# OmapSystem.net
KiCad netlist of a schematic drawn in Altium Designer
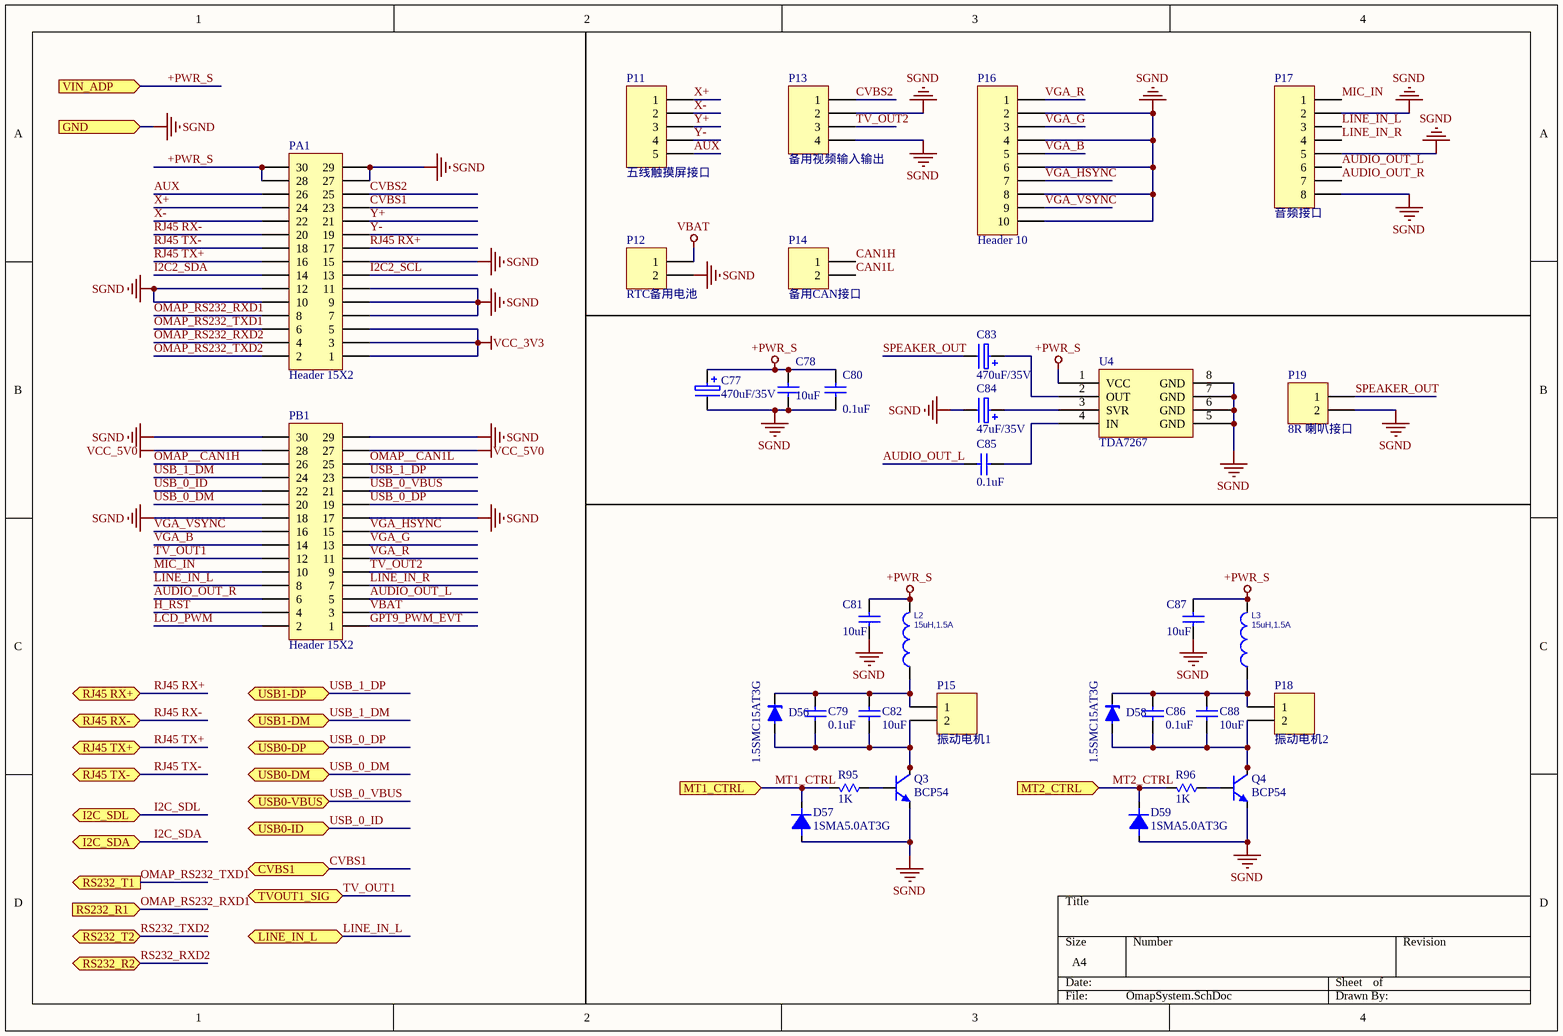
[diagram p0: OmapSystem.SchDoc]

(export (version "E")
  (design (tool "Eeschema 10.0.6"))
  (components
    (comp (ref "C77")
      (value "470uF/35V")
      (footprint "CT7343-E")
      (description "Electrolytic Capacitor")
      (libsource (lib "*") (part "ELECTRO"))
    )
    (comp (ref "C78")
      (value "10uF")
      (footprint "C1206")
      (description "CAP")
      (fields (field (name "PUBLISHER") "Altium Limited"))
      (libsource (lib "Passive Components Class") (part "CAP"))
    )
    (comp (ref "C79")
      (value "0.1uF")
      (footprint "C0805")
      (description "Capacitor")
      (fields (field (name "PUBLISHER") "Altium Limited"))
      (libsource (lib "Miscellaneous Devices") (part "Cap"))
    )
    (comp (ref "C80")
      (value "0.1uF")
      (footprint "C0805")
      (description "CAP")
      (fields (field (name "PUBLISHER") "Altium Limited"))
      (libsource (lib "Passive Components Class") (part "CAP"))
    )
    (comp (ref "C81")
      (value "10uF")
      (footprint "C1206")
      (description "CAP")
      (fields (field (name "PUBLISHER") "Altium Limited"))
      (libsource (lib "Passive Components Class") (part "CAP"))
    )
    (comp (ref "C82")
      (value "10uF")
      (footprint "C1206")
      (description "CAP")
      (fields (field (name "PUBLISHER") "Altium Limited"))
      (libsource (lib "Passive Components Class") (part "CAP"))
    )
    (comp (ref "C83")
      (value "470uF/35V")
      (footprint "CT7343-E")
      (description "Electrolytic Capacitor")
      (libsource (lib "*") (part "ELECTRO"))
    )
    (comp (ref "C84")
      (value "47uF/35V")
      (footprint "CT7343-D")
      (description "Electrolytic Capacitor")
      (libsource (lib "*") (part "ELECTRO"))
    )
    (comp (ref "C85")
      (value "0.1uF")
      (footprint "C0805")
      (description "Capacitor")
      (fields (field (name "PUBLISHER") "Altium Limited"))
      (libsource (lib "Miscellaneous Devices") (part "Cap"))
    )
    (comp (ref "C86")
      (value "0.1uF")
      (footprint "C0805")
      (description "Capacitor")
      (fields (field (name "PUBLISHER") "Altium Limited"))
      (libsource (lib "Miscellaneous Devices") (part "Cap"))
    )
    (comp (ref "C87")
      (value "10uF")
      (footprint "C1206")
      (description "CAP")
      (fields (field (name "PUBLISHER") "Altium Limited"))
      (libsource (lib "Passive Components Class") (part "CAP"))
    )
    (comp (ref "C88")
      (value "10uF")
      (footprint "C1206")
      (description "CAP")
      (fields (field (name "PUBLISHER") "Altium Limited"))
      (libsource (lib "Passive Components Class") (part "CAP"))
    )
    (comp (ref "D56")
      (value "1.5SMC15AT3G")
      (footprint "SMC")
      (description "Small Signal Zener Diodes")
      (libsource (lib "Passive Components Class") (part "DIODE-ZENER"))
    )
    (comp (ref "D57")
      (value "1SMA5.0AT3G")
      (footprint "SMA")
      (description "Diode")
      (libsource (lib "*") (part "DIODE1"))
    )
    (comp (ref "D58")
      (value "1.5SMC15AT3G")
      (footprint "SMC")
      (description "Small Signal Zener Diodes")
      (libsource (lib "Passive Components Class") (part "DIODE-ZENER"))
    )
    (comp (ref "D59")
      (value "1SMA5.0AT3G")
      (footprint "SMA")
      (description "Diode")
      (libsource (lib "*") (part "DIODE1"))
    )
    (comp (ref "L2")
      (value "15uH,1.5A")
      (footprint "L3030-P")
      (description "Inductor")
      (fields (field (name "PUBLISHER") "Altium Limited"))
      (libsource (lib "Miscellaneous Devices") (part "Inductor"))
    )
    (comp (ref "L3")
      (value "15uH,1.5A")
      (footprint "L3030-P")
      (description "Inductor")
      (fields (field (name "PUBLISHER") "Altium Limited"))
      (libsource (lib "Miscellaneous Devices") (part "Inductor"))
    )
    (comp (ref "P11")
      (value "五线触摸屏接口")
      (footprint "DS1X5-2.54")
      (description "Header, 5-Pin")
      (fields (field (name "PUBLISHER") "Altium Limited"))
      (libsource (lib "Miscellaneous Connectors") (part "Header 5"))
    )
    (comp (ref "P12")
      (value "RTC备用电池")
      (footprint "CR2428")
      (description "Header, 2-Pin")
      (fields (field (name "PUBLISHER") "Altium Limited"))
      (libsource (lib "Miscellaneous Connectors") (part "Header 2"))
    )
    (comp (ref "P13")
      (value "备用视频输入输出")
      (footprint "DS1X4-2.54")
      (description "Header, 4-Pin")
      (fields (field (name "PUBLISHER") "Altium Limited"))
      (libsource (lib "Miscellaneous Connectors") (part "Header 4"))
    )
    (comp (ref "P14")
      (value "备用CAN接口")
      (footprint "DS1X2-2.54")
      (description "Header, 2-Pin")
      (fields (field (name "PUBLISHER") "Altium Limited"))
      (libsource (lib "Miscellaneous Connectors") (part "Header 2"))
    )
    (comp (ref "P15")
      (value "振动电机1")
      (footprint "1MM25_2PIN_SMT_R90")
      (description "Header, 2-Pin")
      (fields (field (name "PUBLISHER") "Altium Limited"))
      (libsource (lib "") (part "Header 2_1"))
    )
    (comp (ref "P16")
      (value "Header 10")
      (footprint "DS1X10-2.54")
      (description "Header, 10-Pin")
      (fields (field (name "PUBLISHER") "Altium Limited"))
      (libsource (lib "Miscellaneous Connectors") (part "Header 10"))
    )
    (comp (ref "P17")
      (value "音频接口")
      (footprint "DS1X8-2.54")
      (description "Header, 8-Pin")
      (fields (field (name "PUBLISHER") "Altium Limited"))
      (libsource (lib "Miscellaneous Connectors") (part "Header 8"))
    )
    (comp (ref "P18")
      (value "振动电机2")
      (footprint "1MM25_2PIN_SMT_R90")
      (description "Header, 2-Pin")
      (fields (field (name "PUBLISHER") "Altium Limited"))
      (libsource (lib "") (part "Header 2_1"))
    )
    (comp (ref "P19")
      (value "8R 喇叭接口")
      (footprint "DS1X2-2.54")
      (description "Header, 2-Pin")
      (fields (field (name "PUBLISHER") "Altium Limited"))
      (libsource (lib "Miscellaneous Connectors") (part "Header 2"))
    )
    (comp (ref "PA1")
      (value "Header 15X2")
      (footprint "HDR2X15")
      (description "Header, 15-Pin, Dual row")
      (fields (field (name "PUBLISHER") "Altium Limited"))
      (libsource (lib "Miscellaneous Connectors") (part "Header 15X2"))
    )
    (comp (ref "PB1")
      (value "Header 15X2")
      (footprint "HDR2X15")
      (description "Header, 15-Pin, Dual row")
      (fields (field (name "PUBLISHER") "Altium Limited"))
      (libsource (lib "Miscellaneous Connectors") (part "Header 15X2"))
    )
    (comp (ref "Q3")
      (value "BCP54")
      (footprint "SOT-223")
      (fields (field (name "PUBLISHER") "Altium Limited"))
      (libsource (lib "Passive Components Class") (part "BCP54"))
    )
    (comp (ref "Q4")
      (value "BCP54")
      (footprint "SOT-223")
      (fields (field (name "PUBLISHER") "Altium Limited"))
      (libsource (lib "Passive Components Class") (part "BCP54"))
    )
    (comp (ref "R95")
      (value "1K")
      (footprint "R0805")
      (description "Resistor")
      (fields (field (name "PUBLISHER") "Altium Limited"))
      (libsource (lib "Passive Components Class") (part "RES"))
    )
    (comp (ref "R96")
      (value "1K")
      (footprint "R0805")
      (description "Resistor")
      (fields (field (name "PUBLISHER") "Altium Limited"))
      (libsource (lib "Passive Components Class") (part "RES"))
    )
    (comp (ref "U4")
      (value "TDA7267")
      (footprint "DIP8")
      (description "2W功放芯片")
      (libsource (lib "Power Management Class") (part "TDA7267"))
    )
  )
  (nets
    (net (code "1") (name "+PWR_S") (class "Default")
      (node (ref "C77") (pin "1") (pinfunction "1_1") (pintype "passive"))
      (node (ref "C78") (pin "2") (pinfunction "2_2") (pintype "passive"))
      (node (ref "C80") (pin "2") (pinfunction "2_2") (pintype "passive"))
      (node (ref "C81") (pin "2") (pinfunction "2_2") (pintype "passive"))
      (node (ref "C87") (pin "2") (pinfunction "2_2") (pintype "passive"))
      (node (ref "L2") (pin "2") (pinfunction "2_2") (pintype "passive"))
      (node (ref "L3") (pin "2") (pinfunction "2_2") (pintype "passive"))
      (node (ref "PA1") (pin "28") (pinfunction "28_28") (pintype "passive"))
      (node (ref "PA1") (pin "30") (pinfunction "30_30") (pintype "passive"))
      (node (ref "U4") (pin "1") (pinfunction "VCC_1") (pintype "passive"))
    )
    (net (code "2") (name "/AUDIO_OUT_L") (class "Default")
      (node (ref "C85") (pin "1") (pinfunction "1_1") (pintype "passive"))
      (node (ref "P17") (pin "6") (pinfunction "6_6") (pintype "passive"))
      (node (ref "PB1") (pin "5") (pinfunction "5_5") (pintype "passive"))
    )
    (net (code "3") (name "/AUDIO_OUT_R") (class "Default")
      (node (ref "P17") (pin "7") (pinfunction "7_7") (pintype "passive"))
      (node (ref "PB1") (pin "6") (pinfunction "6_6") (pintype "passive"))
    )
    (net (code "4") (name "/AUX") (class "Default")
      (node (ref "P11") (pin "5") (pinfunction "5_5") (pintype "passive"))
      (node (ref "PA1") (pin "26") (pinfunction "26_26") (pintype "passive"))
    )
    (net (code "5") (name "/CAN1H") (class "Default")
      (node (ref "P14") (pin "1") (pinfunction "1_1") (pintype "passive"))
    )
    (net (code "6") (name "/CAN1L") (class "Default")
      (node (ref "P14") (pin "2") (pinfunction "2_2") (pintype "passive"))
    )
    (net (code "7") (name "/CVBS1") (class "Default")
      (node (ref "PA1") (pin "23") (pinfunction "23_23") (pintype "passive"))
    )
    (net (code "8") (name "/CVBS2") (class "Default")
      (node (ref "P13") (pin "1") (pinfunction "1_1") (pintype "passive"))
      (node (ref "PA1") (pin "25") (pinfunction "25_25") (pintype "passive"))
    )
    (net (code "9") (name "/GPT9_PWM_EVT") (class "Default")
      (node (ref "PB1") (pin "1") (pinfunction "1_1") (pintype "passive"))
    )
    (net (code "10") (name "/H_RST") (class "Default")
      (node (ref "PB1") (pin "4") (pinfunction "4_4") (pintype "passive"))
    )
    (net (code "11") (name "/I2C2_SCL") (class "Default")
      (node (ref "PA1") (pin "13") (pinfunction "13_13") (pintype "passive"))
    )
    (net (code "12") (name "/I2C2_SDA") (class "Default")
      (node (ref "PA1") (pin "14") (pinfunction "14_14") (pintype "passive"))
    )
    (net (code "15") (name "/LCD_PWM") (class "Default")
      (node (ref "PB1") (pin "2") (pinfunction "2_2") (pintype "passive"))
    )
    (net (code "16") (name "/LINE_IN_L") (class "Default")
      (node (ref "P17") (pin "3") (pinfunction "3_3") (pintype "passive"))
      (node (ref "PB1") (pin "8") (pinfunction "8_8") (pintype "passive"))
    )
    (net (code "17") (name "/LINE_IN_R") (class "Default")
      (node (ref "P17") (pin "4") (pinfunction "4_4") (pintype "passive"))
      (node (ref "PB1") (pin "7") (pinfunction "7_7") (pintype "passive"))
    )
    (net (code "18") (name "/MIC_IN") (class "Default")
      (node (ref "P17") (pin "1") (pinfunction "1_1") (pintype "passive"))
      (node (ref "PB1") (pin "10") (pinfunction "10_10") (pintype "passive"))
    )
    (net (code "19") (name "/MT1_CTRL") (class "Default")
      (node (ref "D57") (pin "2") (pinfunction "K_2") (pintype "passive"))
      (node (ref "R95") (pin "2") (pinfunction "2_2") (pintype "passive"))
    )
    (net (code "20") (name "/MT2_CTRL") (class "Default")
      (node (ref "D59") (pin "2") (pinfunction "K_2") (pintype "passive"))
      (node (ref "R96") (pin "2") (pinfunction "2_2") (pintype "passive"))
    )
    (net (code "21") (name "/OMAP_RS232_RXD1") (class "Default")
      (node (ref "PA1") (pin "8") (pinfunction "8_8") (pintype "passive"))
    )
    (net (code "22") (name "/OMAP_RS232_RXD2") (class "Default")
      (node (ref "PA1") (pin "4") (pinfunction "4_4") (pintype "passive"))
    )
    (net (code "23") (name "/OMAP_RS232_TXD1") (class "Default")
      (node (ref "PA1") (pin "6") (pinfunction "6_6") (pintype "passive"))
    )
    (net (code "24") (name "/OMAP_RS232_TXD2") (class "Default")
      (node (ref "PA1") (pin "2") (pinfunction "2_2") (pintype "passive"))
    )
    (net (code "25") (name "/OMAP__CAN1H") (class "Default")
      (node (ref "PB1") (pin "26") (pinfunction "26_26") (pintype "passive"))
    )
    (net (code "26") (name "/OMAP__CAN1L") (class "Default")
      (node (ref "PB1") (pin "25") (pinfunction "25_25") (pintype "passive"))
    )
    (net (code "27") (name "/RJ45 RX+") (class "Default")
      (node (ref "PA1") (pin "17") (pinfunction "17_17") (pintype "passive"))
    )
    (net (code "28") (name "/RJ45 RX-") (class "Default")
      (node (ref "PA1") (pin "20") (pinfunction "20_20") (pintype "passive"))
    )
    (net (code "29") (name "/RJ45 TX+") (class "Default")
      (node (ref "PA1") (pin "16") (pinfunction "16_16") (pintype "passive"))
    )
    (net (code "30") (name "/RJ45 TX-") (class "Default")
      (node (ref "PA1") (pin "18") (pinfunction "18_18") (pintype "passive"))
    )
    (net (code "33") (name "/SPEAKER_OUT") (class "Default")
      (node (ref "C83") (pin "2") (pinfunction "2_2") (pintype "passive"))
      (node (ref "P19") (pin "1") (pinfunction "1_1") (pintype "passive"))
    )
    (net (code "34") (name "/TV_OUT1") (class "Default")
      (node (ref "PB1") (pin "12") (pinfunction "12_12") (pintype "passive"))
    )
    (net (code "35") (name "/TV_OUT2") (class "Default")
      (node (ref "P13") (pin "3") (pinfunction "3_3") (pintype "passive"))
      (node (ref "PB1") (pin "9") (pinfunction "9_9") (pintype "passive"))
    )
    (net (code "36") (name "/USB_0_DM") (class "Default")
      (node (ref "PB1") (pin "20") (pinfunction "20_20") (pintype "passive"))
    )
    (net (code "37") (name "/USB_0_DP") (class "Default")
      (node (ref "PB1") (pin "19") (pinfunction "19_19") (pintype "passive"))
    )
    (net (code "38") (name "/USB_0_ID") (class "Default")
      (node (ref "PB1") (pin "22") (pinfunction "22_22") (pintype "passive"))
    )
    (net (code "39") (name "/USB_0_VBUS") (class "Default")
      (node (ref "PB1") (pin "21") (pinfunction "21_21") (pintype "passive"))
    )
    (net (code "40") (name "/USB_1_DM") (class "Default")
      (node (ref "PB1") (pin "24") (pinfunction "24_24") (pintype "passive"))
    )
    (net (code "41") (name "/USB_1_DP") (class "Default")
      (node (ref "PB1") (pin "23") (pinfunction "23_23") (pintype "passive"))
    )
    (net (code "42") (name "/VGA_B") (class "Default")
      (node (ref "P16") (pin "5") (pinfunction "5_5") (pintype "passive"))
      (node (ref "PB1") (pin "14") (pinfunction "14_14") (pintype "passive"))
    )
    (net (code "43") (name "/VGA_G") (class "Default")
      (node (ref "P16") (pin "3") (pinfunction "3_3") (pintype "passive"))
      (node (ref "PB1") (pin "13") (pinfunction "13_13") (pintype "passive"))
    )
    (net (code "44") (name "/VGA_HSYNC") (class "Default")
      (node (ref "P16") (pin "7") (pinfunction "7_7") (pintype "passive"))
      (node (ref "PB1") (pin "15") (pinfunction "15_15") (pintype "passive"))
    )
    (net (code "45") (name "/VGA_R") (class "Default")
      (node (ref "P16") (pin "1") (pinfunction "1_1") (pintype "passive"))
      (node (ref "PB1") (pin "11") (pinfunction "11_11") (pintype "passive"))
    )
    (net (code "46") (name "/VGA_VSYNC") (class "Default")
      (node (ref "P16") (pin "9") (pinfunction "9_9") (pintype "passive"))
      (node (ref "PB1") (pin "16") (pinfunction "16_16") (pintype "passive"))
    )
    (net (code "47") (name "/X+") (class "Default")
      (node (ref "P11") (pin "1") (pinfunction "1_1") (pintype "passive"))
      (node (ref "PA1") (pin "24") (pinfunction "24_24") (pintype "passive"))
    )
    (net (code "48") (name "/X-") (class "Default")
      (node (ref "P11") (pin "2") (pinfunction "2_2") (pintype "passive"))
      (node (ref "PA1") (pin "22") (pinfunction "22_22") (pintype "passive"))
    )
    (net (code "49") (name "/Y+") (class "Default")
      (node (ref "P11") (pin "3") (pinfunction "3_3") (pintype "passive"))
      (node (ref "PA1") (pin "21") (pinfunction "21_21") (pintype "passive"))
    )
    (net (code "50") (name "/Y-") (class "Default")
      (node (ref "P11") (pin "4") (pinfunction "4_4") (pintype "passive"))
      (node (ref "PA1") (pin "19") (pinfunction "19_19") (pintype "passive"))
    )
    (net (code "51") (name "Net-(D56-A)") (class "Default")
      (node (ref "C79") (pin "1") (pinfunction "1_1") (pintype "passive"))
      (node (ref "C82") (pin "2") (pinfunction "2_2") (pintype "passive"))
      (node (ref "D56") (pin "1") (pinfunction "A_1") (pintype "passive"))
      (node (ref "P15") (pin "2") (pinfunction "2_2") (pintype "passive"))
      (node (ref "Q3") (pin "2") (pinfunction "C_2") (pintype "passive"))
      (node (ref "Q3") (pin "4") (pinfunction "C_4") (pintype "passive"))
    )
    (net (code "52") (name "Net-(D56-K)") (class "Default")
      (node (ref "C79") (pin "2") (pinfunction "2_2") (pintype "passive"))
      (node (ref "C82") (pin "1") (pinfunction "1_1") (pintype "passive"))
      (node (ref "D56") (pin "2") (pinfunction "K_2") (pintype "passive"))
      (node (ref "L2") (pin "1") (pinfunction "1_1") (pintype "passive"))
      (node (ref "P15") (pin "1") (pinfunction "1_1") (pintype "passive"))
    )
    (net (code "53") (name "Net-(D58-A)") (class "Default")
      (node (ref "C86") (pin "1") (pinfunction "1_1") (pintype "passive"))
      (node (ref "C88") (pin "2") (pinfunction "2_2") (pintype "passive"))
      (node (ref "D58") (pin "1") (pinfunction "A_1") (pintype "passive"))
      (node (ref "P18") (pin "2") (pinfunction "2_2") (pintype "passive"))
      (node (ref "Q4") (pin "2") (pinfunction "C_2") (pintype "passive"))
      (node (ref "Q4") (pin "4") (pinfunction "C_4") (pintype "passive"))
    )
    (net (code "54") (name "Net-(D58-K)") (class "Default")
      (node (ref "C86") (pin "2") (pinfunction "2_2") (pintype "passive"))
      (node (ref "C88") (pin "1") (pinfunction "1_1") (pintype "passive"))
      (node (ref "D58") (pin "2") (pinfunction "K_2") (pintype "passive"))
      (node (ref "L3") (pin "1") (pinfunction "1_1") (pintype "passive"))
      (node (ref "P18") (pin "1") (pinfunction "1_1") (pintype "passive"))
    )
    (net (code "55") (name "Net-(Q3-B)") (class "Default")
      (node (ref "Q3") (pin "1") (pinfunction "B_1") (pintype "passive"))
      (node (ref "R95") (pin "1") (pinfunction "1_1") (pintype "passive"))
    )
    (net (code "56") (name "Net-(Q4-B)") (class "Default")
      (node (ref "Q4") (pin "1") (pinfunction "B_1") (pintype "passive"))
      (node (ref "R96") (pin "1") (pinfunction "1_1") (pintype "passive"))
    )
    (net (code "57") (name "Net-(U4-IN)") (class "Default")
      (node (ref "C85") (pin "2") (pinfunction "2_2") (pintype "passive"))
      (node (ref "U4") (pin "4") (pinfunction "IN_4") (pintype "passive"))
    )
    (net (code "58") (name "Net-(U4-OUT)") (class "Default")
      (node (ref "C83") (pin "1") (pinfunction "1_1") (pintype "passive"))
      (node (ref "U4") (pin "2") (pinfunction "OUT_2") (pintype "passive"))
    )
    (net (code "59") (name "Net-(U4-SVR)") (class "Default")
      (node (ref "C84") (pin "1") (pinfunction "1_1") (pintype "passive"))
      (node (ref "U4") (pin "3") (pinfunction "SVR_3") (pintype "passive"))
    )
    (net (code "60") (name "SGND") (class "Default")
      (node (ref "C77") (pin "2") (pinfunction "2_2") (pintype "passive"))
      (node (ref "C78") (pin "1") (pinfunction "1_1") (pintype "passive"))
      (node (ref "C80") (pin "1") (pinfunction "1_1") (pintype "passive"))
      (node (ref "C81") (pin "1") (pinfunction "1_1") (pintype "passive"))
      (node (ref "C84") (pin "2") (pinfunction "2_2") (pintype "passive"))
      (node (ref "C87") (pin "1") (pinfunction "1_1") (pintype "passive"))
      (node (ref "D57") (pin "1") (pinfunction "A_1") (pintype "passive"))
      (node (ref "D59") (pin "1") (pinfunction "A_1") (pintype "passive"))
      (node (ref "P12") (pin "2") (pinfunction "2_2") (pintype "passive"))
      (node (ref "P13") (pin "2") (pinfunction "2_2") (pintype "passive"))
      (node (ref "P13") (pin "4") (pinfunction "4_4") (pintype "passive"))
      (node (ref "P16") (pin "10") (pinfunction "10_10") (pintype "passive"))
      (node (ref "P16") (pin "2") (pinfunction "2_2") (pintype "passive"))
      (node (ref "P16") (pin "4") (pinfunction "4_4") (pintype "passive"))
      (node (ref "P16") (pin "6") (pinfunction "6_6") (pintype "passive"))
      (node (ref "P16") (pin "8") (pinfunction "8_8") (pintype "passive"))
      (node (ref "P17") (pin "2") (pinfunction "2_2") (pintype "passive"))
      (node (ref "P17") (pin "5") (pinfunction "5_5") (pintype "passive"))
      (node (ref "P17") (pin "8") (pinfunction "8_8") (pintype "passive"))
      (node (ref "P19") (pin "2") (pinfunction "2_2") (pintype "passive"))
      (node (ref "PA1") (pin "10") (pinfunction "10_10") (pintype "passive"))
      (node (ref "PA1") (pin "11") (pinfunction "11_11") (pintype "passive"))
      (node (ref "PA1") (pin "12") (pinfunction "12_12") (pintype "passive"))
      (node (ref "PA1") (pin "15") (pinfunction "15_15") (pintype "passive"))
      (node (ref "PA1") (pin "27") (pinfunction "27_27") (pintype "passive"))
      (node (ref "PA1") (pin "29") (pinfunction "29_29") (pintype "passive"))
      (node (ref "PA1") (pin "7") (pinfunction "7_7") (pintype "passive"))
      (node (ref "PA1") (pin "9") (pinfunction "9_9") (pintype "passive"))
      (node (ref "PB1") (pin "17") (pinfunction "17_17") (pintype "passive"))
      (node (ref "PB1") (pin "18") (pinfunction "18_18") (pintype "passive"))
      (node (ref "PB1") (pin "29") (pinfunction "29_29") (pintype "passive"))
      (node (ref "PB1") (pin "30") (pinfunction "30_30") (pintype "passive"))
      (node (ref "Q3") (pin "3") (pinfunction "E_3") (pintype "passive"))
      (node (ref "Q4") (pin "3") (pinfunction "E_3") (pintype "passive"))
      (node (ref "U4") (pin "5") (pinfunction "GND_5") (pintype "passive"))
      (node (ref "U4") (pin "6") (pinfunction "GND_6") (pintype "passive"))
      (node (ref "U4") (pin "7") (pinfunction "GND_7") (pintype "passive"))
      (node (ref "U4") (pin "8") (pinfunction "GND_8") (pintype "passive"))
    )
    (net (code "61") (name "VBAT") (class "Default")
      (node (ref "P12") (pin "1") (pinfunction "1_1") (pintype "passive"))
      (node (ref "PB1") (pin "3") (pinfunction "3_3") (pintype "passive"))
    )
    (net (code "62") (name "VCC_3V3") (class "Default")
      (node (ref "PA1") (pin "1") (pinfunction "1_1") (pintype "passive"))
      (node (ref "PA1") (pin "3") (pinfunction "3_3") (pintype "passive"))
      (node (ref "PA1") (pin "5") (pinfunction "5_5") (pintype "passive"))
    )
    (net (code "63") (name "VCC_5V0") (class "Default")
      (node (ref "PB1") (pin "27") (pinfunction "27_27") (pintype "passive"))
      (node (ref "PB1") (pin "28") (pinfunction "28_28") (pintype "passive"))
    )
  )
)
